# lt1619-breakout.net
KiCad netlist of a schematic drawn in EAGLE
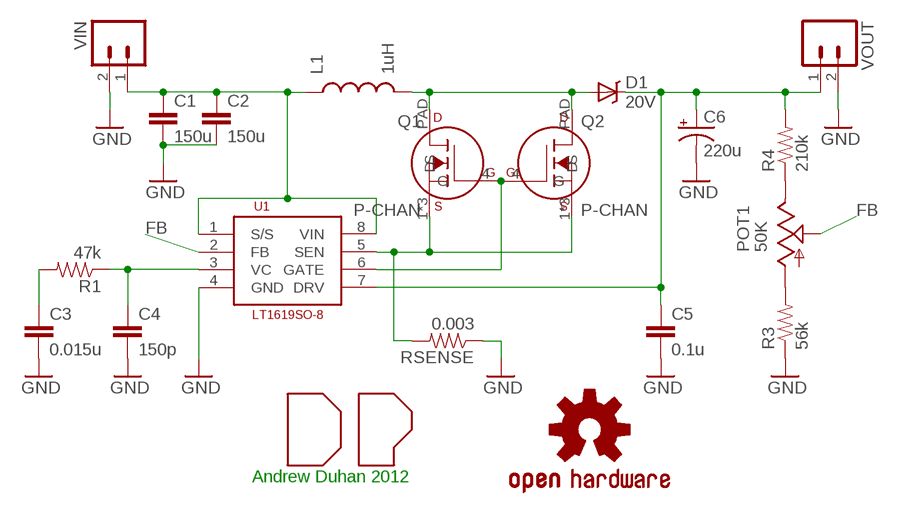
[diagram p0: schematic, sheet 1]

(export (version "E")
  (design (tool "Eeschema 10.0.6"))
  (components
    (comp (ref "C1")
      (value "150u")
      (footprint "eagle-import:1210")
      (libsource (lib "eagle-import") (part "SparkFun-Passives_CAP1210"))
    )
    (comp (ref "C2")
      (value "150u")
      (footprint "eagle-import:1210")
      (libsource (lib "eagle-import") (part "SparkFun-Passives_CAP1210"))
    )
    (comp (ref "C3")
      (value "0.015u")
      (footprint "eagle-import:0603-CAP")
      (libsource (lib "eagle-import") (part "CAP0603-CAP"))
    )
    (comp (ref "C4")
      (value "150p")
      (footprint "eagle-import:0603-CAP")
      (libsource (lib "eagle-import") (part "CAP0603-CAP"))
    )
    (comp (ref "C5")
      (value "0.1u")
      (footprint "eagle-import:0603-CAP")
      (libsource (lib "eagle-import") (part "CAP0603-CAP"))
    )
    (comp (ref "C6")
      (value "220u")
      (footprint "eagle-import:EIA7343")
      (libsource (lib "eagle-import") (part "CAP_POL7343"))
    )
    (comp (ref "D1")
      (value "20V")
      (footprint "eagle-import:DO-214AB")
      (libsource (lib "eagle-import") (part "SCHOTTKYDO214AB"))
    )
    (comp (ref "L1")
      (value "1uH")
      (footprint "eagle-import:INDUCTOR_10.9X10.0")
      (libsource (lib "eagle-import") (part "INDUCTOR-SMD-MED4"))
    )
    (comp (ref "POT1")
      (value "50K")
      (footprint "eagle-import:POT-TOP-BOURNS")
      (libsource (lib "eagle-import") (part "POT3310Y-001"))
    )
    (comp (ref "Q1")
      (value "P-CHAN")
      (footprint "eagle-import:LFPAK")
      (libsource (lib "eagle-import") (part "MOSFET_NP-S08"))
    )
    (comp (ref "Q2")
      (value "P-CHAN")
      (footprint "eagle-import:LFPAK")
      (libsource (lib "eagle-import") (part "MOSFET_NP-S08"))
    )
    (comp (ref "R1")
      (value "47k")
      (footprint "eagle-import:0603-RES")
      (libsource (lib "eagle-import") (part "RESISTOR0603-RES"))
    )
    (comp (ref "R3")
      (value "56k")
      (footprint "eagle-import:0603-RES")
      (libsource (lib "eagle-import") (part "RESISTOR0603-RES"))
    )
    (comp (ref "R4")
      (value "210k")
      (footprint "eagle-import:0603-RES")
      (libsource (lib "eagle-import") (part "RESISTOR0603-RES"))
    )
    (comp (ref "RSENSE")
      (value "0.003")
      (footprint "eagle-import:1206")
      (libsource (lib "eagle-import") (part "RESISTOR1206"))
    )
    (comp (ref "U$2")
      (value "DP_LOGO")
      (footprint "eagle-import:DP_LOGO")
      (libsource (lib "eagle-import") (part "DP_LOGO"))
    )
    (comp (ref "U$4")
      (value "OSHW-LOGOM")
      (footprint "eagle-import:OSHW-LOGO-M")
      (libsource (lib "eagle-import") (part "OSHW-LOGOM"))
    )
    (comp (ref "U1")
      (value "LT1619SO-8")
      (footprint "eagle-import:SOIC-08")
      (libsource (lib "eagle-import") (part "LT1619SO-8"))
    )
    (comp (ref "VIN")
      (value "M02PTH")
      (footprint "eagle-import:1X02")
      (libsource (lib "eagle-import") (part "M02PTH"))
    )
    (comp (ref "VOUT")
      (value "M02PTH")
      (footprint "eagle-import:1X02")
      (libsource (lib "eagle-import") (part "M02PTH"))
    )
  )
  (nets
    (net (code "1") (name "/FB") (class "Default")
      (node (ref "POT1") (pin "2") (pinfunction "W_2") (pintype "passive"))
      (node (ref "U1") (pin "2") (pinfunction "FB_2") (pintype "bidirectional"))
    )
    (net (code "2") (name "GND") (class "Default")
      (node (ref "C1") (pin "2") (pinfunction "2_2") (pintype "passive"))
      (node (ref "C2") (pin "2") (pinfunction "2_2") (pintype "passive"))
      (node (ref "C3") (pin "2") (pinfunction "2_2") (pintype "passive"))
      (node (ref "C4") (pin "2") (pinfunction "2_2") (pintype "passive"))
      (node (ref "C5") (pin "2") (pinfunction "2_2") (pintype "passive"))
      (node (ref "C6") (pin "C") (pinfunction "-_C") (pintype "passive"))
      (node (ref "R3") (pin "1") (pinfunction "1_1") (pintype "passive"))
      (node (ref "RSENSE") (pin "1") (pinfunction "1_1") (pintype "passive"))
      (node (ref "U1") (pin "4") (pinfunction "GND_4") (pintype "bidirectional"))
      (node (ref "VIN") (pin "2") (pinfunction "2_2") (pintype "passive"))
      (node (ref "VOUT") (pin "2") (pinfunction "2_2") (pintype "passive"))
    )
    (net (code "3") (name "Net-(C3-Pad1)") (class "Default")
      (node (ref "C3") (pin "1") (pinfunction "1_1") (pintype "passive"))
      (node (ref "R1") (pin "2") (pinfunction "2_2") (pintype "passive"))
    )
    (net (code "4") (name "Net-(C6-+)") (class "Default")
      (node (ref "C5") (pin "1") (pinfunction "1_1") (pintype "passive"))
      (node (ref "C6") (pin "A") (pinfunction "+_A") (pintype "passive"))
      (node (ref "D1") (pin "C") (pinfunction "C_C") (pintype "passive"))
      (node (ref "R4") (pin "2") (pinfunction "2_2") (pintype "passive"))
      (node (ref "U1") (pin "7") (pinfunction "DRV_7") (pintype "bidirectional"))
      (node (ref "VOUT") (pin "1") (pinfunction "1_1") (pintype "passive"))
    )
    (net (code "5") (name "Net-(L1-1)") (class "Default")
      (node (ref "C1") (pin "1") (pinfunction "1_1") (pintype "passive"))
      (node (ref "C2") (pin "1") (pinfunction "1_1") (pintype "passive"))
      (node (ref "L1") (pin "P$1") (pinfunction "1_P$1") (pintype "passive"))
      (node (ref "U1") (pin "1") (pinfunction "S/S_1") (pintype "bidirectional"))
      (node (ref "U1") (pin "8") (pinfunction "VIN_8") (pintype "bidirectional"))
      (node (ref "VIN") (pin "1") (pinfunction "1_1") (pintype "passive"))
    )
    (net (code "6") (name "Net-(L1-2)") (class "Default")
      (node (ref "D1") (pin "A") (pinfunction "A_A") (pintype "passive"))
      (node (ref "L1") (pin "P$2") (pinfunction "2_P$2") (pintype "passive"))
      (node (ref "Q1") (pin "PAD") (pinfunction "D_PAD") (pintype "bidirectional"))
      (node (ref "Q2") (pin "PAD") (pinfunction "D_PAD") (pintype "bidirectional"))
    )
    (net (code "7") (name "Net-(POT1-A)") (class "Default")
      (node (ref "POT1") (pin "1") (pinfunction "A_1") (pintype "passive"))
      (node (ref "R3") (pin "2") (pinfunction "2_2") (pintype "passive"))
    )
    (net (code "8") (name "Net-(POT1-B)") (class "Default")
      (node (ref "POT1") (pin "3") (pinfunction "B_3") (pintype "passive"))
      (node (ref "R4") (pin "1") (pinfunction "1_1") (pintype "passive"))
    )
    (net (code "9") (name "Net-(Q1-G)") (class "Default")
      (node (ref "Q1") (pin "4") (pinfunction "G_4") (pintype "bidirectional"))
      (node (ref "Q2") (pin "4") (pinfunction "G_4") (pintype "bidirectional"))
      (node (ref "U1") (pin "6") (pinfunction "GATE_6") (pintype "bidirectional"))
    )
    (net (code "10") (name "Net-(U1-SEN)") (class "Default")
      (node (ref "Q1") (pin "1") (pinfunction "S_1") (pintype "bidirectional"))
      (node (ref "Q1") (pin "2") (pinfunction "S_2") (pintype "bidirectional"))
      (node (ref "Q1") (pin "3") (pinfunction "S_3") (pintype "bidirectional"))
      (node (ref "Q2") (pin "1") (pinfunction "S_1") (pintype "bidirectional"))
      (node (ref "Q2") (pin "2") (pinfunction "S_2") (pintype "bidirectional"))
      (node (ref "Q2") (pin "3") (pinfunction "S_3") (pintype "bidirectional"))
      (node (ref "RSENSE") (pin "2") (pinfunction "2_2") (pintype "passive"))
      (node (ref "U1") (pin "5") (pinfunction "SEN_5") (pintype "bidirectional"))
    )
    (net (code "11") (name "Net-(U1-VC)") (class "Default")
      (node (ref "C4") (pin "1") (pinfunction "1_1") (pintype "passive"))
      (node (ref "R1") (pin "1") (pinfunction "1_1") (pintype "passive"))
      (node (ref "U1") (pin "3") (pinfunction "VC_3") (pintype "bidirectional"))
    )
  )
)
